# Werkstatt_Provisions_v_09.net
KiCad netlist of a schematic drawn in EAGLE
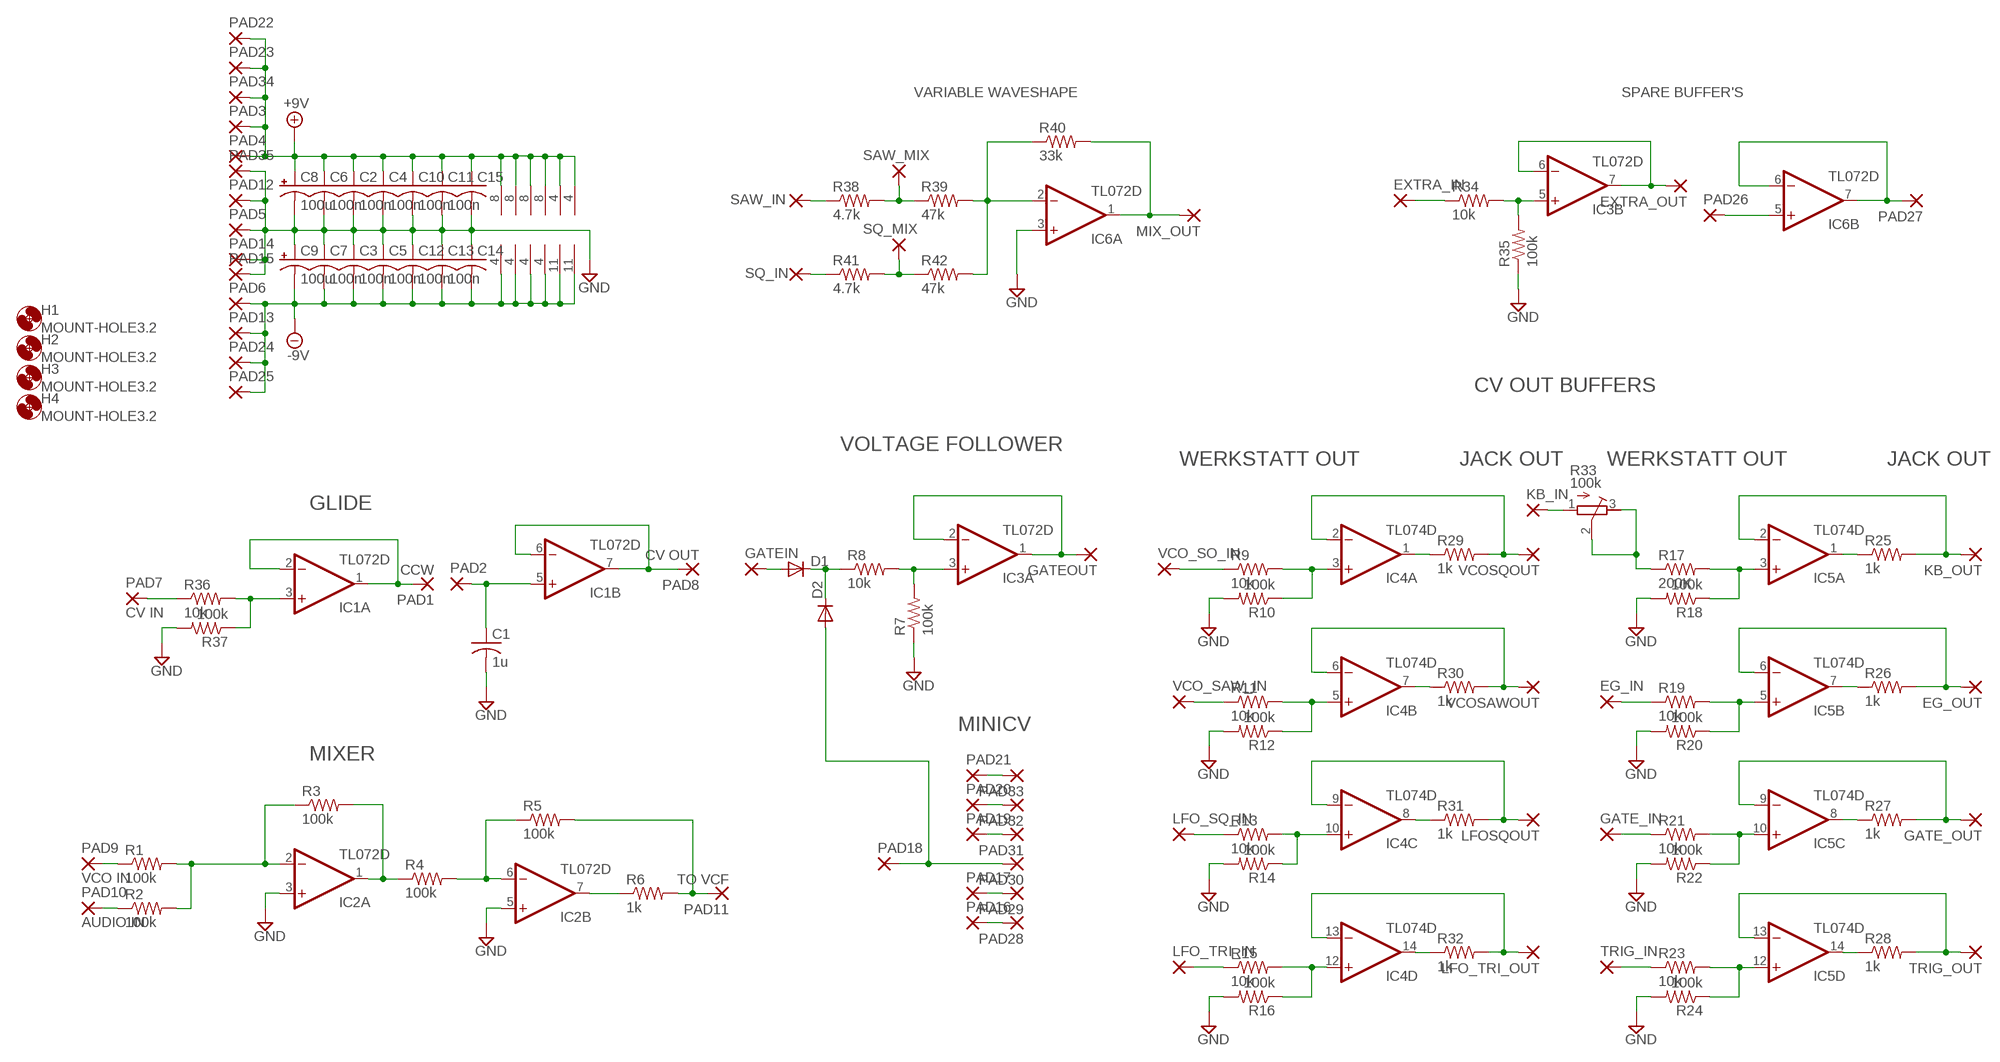
[diagram p0: schematic, sheet 1]

(export (version "E")
  (design (tool "Eeschema 10.0.6"))
  (components
    (comp (ref "C1")
      (value "1u")
      (footprint "eagle-import:C0805K")
      (libsource (lib "eagle-import") (part "C-USC0805K"))
    )
    (comp (ref "C2")
      (value "100n")
      (footprint "eagle-import:C0805K")
      (libsource (lib "eagle-import") (part "C-USC0805K"))
    )
    (comp (ref "C3")
      (value "100n")
      (footprint "eagle-import:C0805K")
      (libsource (lib "eagle-import") (part "C-USC0805K"))
    )
    (comp (ref "C4")
      (value "100n")
      (footprint "eagle-import:C0805K")
      (libsource (lib "eagle-import") (part "C-USC0805K"))
    )
    (comp (ref "C5")
      (value "100n")
      (footprint "eagle-import:C0805K")
      (libsource (lib "eagle-import") (part "C-USC0805K"))
    )
    (comp (ref "C6")
      (value "100n")
      (footprint "eagle-import:C0805K")
      (libsource (lib "eagle-import") (part "C-USC0805K"))
    )
    (comp (ref "C7")
      (value "100n")
      (footprint "eagle-import:C0805K")
      (libsource (lib "eagle-import") (part "C-USC0805K"))
    )
    (comp (ref "C8")
      (value "100u")
      (footprint "eagle-import:PANASONIC_D")
      (libsource (lib "eagle-import") (part "CPOL-USD"))
    )
    (comp (ref "C9")
      (value "100u")
      (footprint "eagle-import:PANASONIC_D")
      (libsource (lib "eagle-import") (part "CPOL-USD"))
    )
    (comp (ref "C10")
      (value "100n")
      (footprint "eagle-import:C0805K")
      (libsource (lib "eagle-import") (part "C-USC0805K"))
    )
    (comp (ref "C11")
      (value "100n")
      (footprint "eagle-import:C0805K")
      (libsource (lib "eagle-import") (part "C-USC0805K"))
    )
    (comp (ref "C12")
      (value "100n")
      (footprint "eagle-import:C0805K")
      (libsource (lib "eagle-import") (part "C-USC0805K"))
    )
    (comp (ref "C13")
      (value "100n")
      (footprint "eagle-import:C0805K")
      (libsource (lib "eagle-import") (part "C-USC0805K"))
    )
    (comp (ref "C14")
      (value "C-USC0805")
      (footprint "eagle-import:C0805")
      (libsource (lib "eagle-import") (part "C-USC0805"))
    )
    (comp (ref "C15")
      (value "C-USC0805")
      (footprint "eagle-import:C0805")
      (libsource (lib "eagle-import") (part "C-USC0805"))
    )
    (comp (ref "D1")
      (value "DIODE-SOD323-W")
      (footprint "eagle-import:SOD323-W")
      (libsource (lib "eagle-import") (part "DIODE-SOD323-W"))
    )
    (comp (ref "D2")
      (value "DIODE-SOD323-W")
      (footprint "eagle-import:SOD323-W")
      (libsource (lib "eagle-import") (part "DIODE-SOD323-W"))
    )
    (comp (ref "EG_IN")
      (value "2,0/0,9-O")
      (footprint "eagle-import:2,0_0,9-O")
      (libsource (lib "eagle-import") (part "2,0/0,9-O"))
    )
    (comp (ref "EG_OUT")
      (value "2,0/0,9-O")
      (footprint "eagle-import:2,0_0,9-O")
      (libsource (lib "eagle-import") (part "2,0/0,9-O"))
    )
    (comp (ref "EXTRA_IN")
      (value "2,0/0,9-O")
      (footprint "eagle-import:2,0_0,9-O")
      (libsource (lib "eagle-import") (part "2,0/0,9-O"))
    )
    (comp (ref "EXTRA_OUT")
      (value "2,0/0,9-O")
      (footprint "eagle-import:2,0_0,9-O")
      (libsource (lib "eagle-import") (part "2,0/0,9-O"))
    )
    (comp (ref "GATEIN")
      (value "2,0/0,9-O")
      (footprint "eagle-import:2,0_0,9-O")
      (libsource (lib "eagle-import") (part "2,0/0,9-O"))
    )
    (comp (ref "GATEOUT")
      (value "2,0/0,9-O")
      (footprint "eagle-import:2,0_0,9-O")
      (libsource (lib "eagle-import") (part "2,0/0,9-O"))
    )
    (comp (ref "GATE_IN")
      (value "2,0/0,9-O")
      (footprint "eagle-import:2,0_0,9-O")
      (libsource (lib "eagle-import") (part "2,0/0,9-O"))
    )
    (comp (ref "GATE_OUT")
      (value "2,0/0,9-O")
      (footprint "eagle-import:2,0_0,9-O")
      (libsource (lib "eagle-import") (part "2,0/0,9-O"))
    )
    (comp (ref "H1")
      (value "MOUNT-HOLE3.2")
      (footprint "eagle-import:3,2")
      (libsource (lib "eagle-import") (part "MOUNT-HOLE3.2"))
    )
    (comp (ref "H2")
      (value "MOUNT-HOLE3.2")
      (footprint "eagle-import:3,2")
      (libsource (lib "eagle-import") (part "MOUNT-HOLE3.2"))
    )
    (comp (ref "H3")
      (value "MOUNT-HOLE3.2")
      (footprint "eagle-import:3,2")
      (libsource (lib "eagle-import") (part "MOUNT-HOLE3.2"))
    )
    (comp (ref "H4")
      (value "MOUNT-HOLE3.2")
      (footprint "eagle-import:3,2")
      (libsource (lib "eagle-import") (part "MOUNT-HOLE3.2"))
    )
    (comp (ref "IC1")
      (value "TL072D")
      (footprint "eagle-import:SO08")
      (libsource (lib "eagle-import") (part "TL072D"))
    )
    (comp (ref "IC2")
      (value "TL072D")
      (footprint "eagle-import:SO08")
      (libsource (lib "eagle-import") (part "TL072D"))
    )
    (comp (ref "IC3")
      (value "TL072D")
      (footprint "eagle-import:SO08")
      (libsource (lib "eagle-import") (part "TL072D"))
    )
    (comp (ref "IC4")
      (value "TL074D")
      (footprint "eagle-import:SO14")
      (libsource (lib "eagle-import") (part "TL074D"))
    )
    (comp (ref "IC5")
      (value "TL074D")
      (footprint "eagle-import:SO14")
      (libsource (lib "eagle-import") (part "TL074D"))
    )
    (comp (ref "IC6")
      (value "TL072D")
      (footprint "eagle-import:SO08")
      (libsource (lib "eagle-import") (part "TL072D"))
    )
    (comp (ref "KB_IN")
      (value "2,0/0,9-O")
      (footprint "eagle-import:2,0_0,9-O")
      (libsource (lib "eagle-import") (part "2,0/0,9-O"))
    )
    (comp (ref "KB_OUT")
      (value "2,0/0,9-O")
      (footprint "eagle-import:2,0_0,9-O")
      (libsource (lib "eagle-import") (part "2,0/0,9-O"))
    )
    (comp (ref "LFOSQOUT")
      (value "2,0/0,9-O")
      (footprint "eagle-import:2,0_0,9-O")
      (libsource (lib "eagle-import") (part "2,0/0,9-O"))
    )
    (comp (ref "LFO_SQ_IN")
      (value "2,0/0,9-O")
      (footprint "eagle-import:2,0_0,9-O")
      (libsource (lib "eagle-import") (part "2,0/0,9-O"))
    )
    (comp (ref "LFO_TRI_IN")
      (value "2,0/0,9-O")
      (footprint "eagle-import:2,0_0,9-O")
      (libsource (lib "eagle-import") (part "2,0/0,9-O"))
    )
    (comp (ref "LFO_TRI_OUT")
      (value "2,0/0,9-O")
      (footprint "eagle-import:2,0_0,9-O")
      (libsource (lib "eagle-import") (part "2,0/0,9-O"))
    )
    (comp (ref "MIX_OUT")
      (value "2,0/0,9-O")
      (footprint "eagle-import:2,0_0,9-O")
      (libsource (lib "eagle-import") (part "2,0/0,9-O"))
    )
    (comp (ref "PAD1")
      (value "CCW")
      (footprint "eagle-import:2,0_0,9-O")
      (libsource (lib "eagle-import") (part "2,0/0,9-O"))
    )
    (comp (ref "PAD2")
      (value "2,0/0,9-O")
      (footprint "eagle-import:2,0_0,9-O")
      (libsource (lib "eagle-import") (part "2,0/0,9-O"))
    )
    (comp (ref "PAD3")
      (value "2,0/0,9-O")
      (footprint "eagle-import:2,0_0,9-O")
      (libsource (lib "eagle-import") (part "2,0/0,9-O"))
    )
    (comp (ref "PAD4")
      (value "2,0/0,9-O")
      (footprint "eagle-import:2,0_0,9-O")
      (libsource (lib "eagle-import") (part "2,0/0,9-O"))
    )
    (comp (ref "PAD5")
      (value "2,0/0,9-O")
      (footprint "eagle-import:2,0_0,9-O")
      (libsource (lib "eagle-import") (part "2,0/0,9-O"))
    )
    (comp (ref "PAD6")
      (value "2,0/0,9-O")
      (footprint "eagle-import:2,0_0,9-O")
      (libsource (lib "eagle-import") (part "2,0/0,9-O"))
    )
    (comp (ref "PAD7")
      (value "CV IN")
      (footprint "eagle-import:2,0_0,9-O")
      (libsource (lib "eagle-import") (part "2,0/0,9-O"))
    )
    (comp (ref "PAD8")
      (value "CV OUT")
      (footprint "eagle-import:2,0_0,9-O")
      (libsource (lib "eagle-import") (part "2,0/0,9-O"))
    )
    (comp (ref "PAD9")
      (value "VCO IN")
      (footprint "eagle-import:2,0_0,9-O")
      (libsource (lib "eagle-import") (part "2,0/0,9-O"))
    )
    (comp (ref "PAD10")
      (value "AUDIO IN")
      (footprint "eagle-import:2,0_0,9-O")
      (libsource (lib "eagle-import") (part "2,0/0,9-O"))
    )
    (comp (ref "PAD11")
      (value "TO VCF")
      (footprint "eagle-import:2,0_0,9-O")
      (libsource (lib "eagle-import") (part "2,0/0,9-O"))
    )
    (comp (ref "PAD12")
      (value "2,0/0,9-O")
      (footprint "eagle-import:2,0_0,9-O")
      (libsource (lib "eagle-import") (part "2,0/0,9-O"))
    )
    (comp (ref "PAD13")
      (value "2,0/0,9-O")
      (footprint "eagle-import:2,0_0,9-O")
      (libsource (lib "eagle-import") (part "2,0/0,9-O"))
    )
    (comp (ref "PAD14")
      (value "2,0/0,9-O")
      (footprint "eagle-import:2,0_0,9-O")
      (libsource (lib "eagle-import") (part "2,0/0,9-O"))
    )
    (comp (ref "PAD15")
      (value "2,0/0,9-O")
      (footprint "eagle-import:2,0_0,9-O")
      (libsource (lib "eagle-import") (part "2,0/0,9-O"))
    )
    (comp (ref "PAD16")
      (value "2,0/0,9-O")
      (footprint "eagle-import:2,0_0,9-O")
      (libsource (lib "eagle-import") (part "2,0/0,9-O"))
    )
    (comp (ref "PAD17")
      (value "2,0/0,9-O")
      (footprint "eagle-import:2,0_0,9-O")
      (libsource (lib "eagle-import") (part "2,0/0,9-O"))
    )
    (comp (ref "PAD18")
      (value "2,0/0,9-O")
      (footprint "eagle-import:2,0_0,9-O")
      (libsource (lib "eagle-import") (part "2,0/0,9-O"))
    )
    (comp (ref "PAD19")
      (value "2,0/0,9-O")
      (footprint "eagle-import:2,0_0,9-O")
      (libsource (lib "eagle-import") (part "2,0/0,9-O"))
    )
    (comp (ref "PAD20")
      (value "2,0/0,9-O")
      (footprint "eagle-import:2,0_0,9-O")
      (libsource (lib "eagle-import") (part "2,0/0,9-O"))
    )
    (comp (ref "PAD21")
      (value "2,0/0,9-O")
      (footprint "eagle-import:2,0_0,9-O")
      (libsource (lib "eagle-import") (part "2,0/0,9-O"))
    )
    (comp (ref "PAD22")
      (value "2,0/0,9-O")
      (footprint "eagle-import:2,0_0,9-O")
      (libsource (lib "eagle-import") (part "2,0/0,9-O"))
    )
    (comp (ref "PAD23")
      (value "2,0/0,9-O")
      (footprint "eagle-import:2,0_0,9-O")
      (libsource (lib "eagle-import") (part "2,0/0,9-O"))
    )
    (comp (ref "PAD24")
      (value "2,0/0,9-O")
      (footprint "eagle-import:2,0_0,9-O")
      (libsource (lib "eagle-import") (part "2,0/0,9-O"))
    )
    (comp (ref "PAD25")
      (value "2,0/0,9-O")
      (footprint "eagle-import:2,0_0,9-O")
      (libsource (lib "eagle-import") (part "2,0/0,9-O"))
    )
    (comp (ref "PAD26")
      (value "2,0/0,9-O")
      (footprint "eagle-import:2,0_0,9-O")
      (libsource (lib "eagle-import") (part "2,0/0,9-O"))
    )
    (comp (ref "PAD27")
      (value "2,0/0,9-O")
      (footprint "eagle-import:2,0_0,9-O")
      (libsource (lib "eagle-import") (part "2,0/0,9-O"))
    )
    (comp (ref "PAD28")
      (value "1,6/0,8")
      (footprint "eagle-import:1,6_0,8")
      (libsource (lib "eagle-import") (part "1,6/0,8"))
    )
    (comp (ref "PAD29")
      (value "1,6/0,8")
      (footprint "eagle-import:1,6_0,8")
      (libsource (lib "eagle-import") (part "1,6/0,8"))
    )
    (comp (ref "PAD30")
      (value "1,6/0,8")
      (footprint "eagle-import:1,6_0,8")
      (libsource (lib "eagle-import") (part "1,6/0,8"))
    )
    (comp (ref "PAD31")
      (value "1,6/0,8")
      (footprint "eagle-import:1,6_0,8")
      (libsource (lib "eagle-import") (part "1,6/0,8"))
    )
    (comp (ref "PAD32")
      (value "1,6/0,8")
      (footprint "eagle-import:1,6_0,8")
      (libsource (lib "eagle-import") (part "1,6/0,8"))
    )
    (comp (ref "PAD33")
      (value "1,6/0,8")
      (footprint "eagle-import:1,6_0,8")
      (libsource (lib "eagle-import") (part "1,6/0,8"))
    )
    (comp (ref "PAD34")
      (value "1,6/0,8")
      (footprint "eagle-import:1,6_0,8")
      (libsource (lib "eagle-import") (part "1,6/0,8"))
    )
    (comp (ref "PAD35")
      (value "1,6/0,8")
      (footprint "eagle-import:1,6_0,8")
      (libsource (lib "eagle-import") (part "1,6/0,8"))
    )
    (comp (ref "R1")
      (value "100k")
      (footprint "eagle-import:M0805")
      (libsource (lib "eagle-import") (part "R-US_M0805"))
    )
    (comp (ref "R2")
      (value "100k")
      (footprint "eagle-import:M0805")
      (libsource (lib "eagle-import") (part "R-US_M0805"))
    )
    (comp (ref "R3")
      (value "100k")
      (footprint "eagle-import:M0805")
      (libsource (lib "eagle-import") (part "R-US_M0805"))
    )
    (comp (ref "R4")
      (value "100k")
      (footprint "eagle-import:M0805")
      (libsource (lib "eagle-import") (part "R-US_M0805"))
    )
    (comp (ref "R5")
      (value "100k")
      (footprint "eagle-import:M0805")
      (libsource (lib "eagle-import") (part "R-US_M0805"))
    )
    (comp (ref "R6")
      (value "1k")
      (footprint "eagle-import:M0805")
      (libsource (lib "eagle-import") (part "R-US_M0805"))
    )
    (comp (ref "R7")
      (value "100k")
      (footprint "eagle-import:M0805")
      (libsource (lib "eagle-import") (part "R-US_M0805"))
    )
    (comp (ref "R8")
      (value "10k")
      (footprint "eagle-import:M0805")
      (libsource (lib "eagle-import") (part "R-US_M0805"))
    )
    (comp (ref "R9")
      (value "10k")
      (footprint "eagle-import:M0805")
      (libsource (lib "eagle-import") (part "R-US_M0805"))
    )
    (comp (ref "R10")
      (value "100k")
      (footprint "eagle-import:M0805")
      (libsource (lib "eagle-import") (part "R-US_M0805"))
    )
    (comp (ref "R11")
      (value "10k")
      (footprint "eagle-import:M0805")
      (libsource (lib "eagle-import") (part "R-US_M0805"))
    )
    (comp (ref "R12")
      (value "100k")
      (footprint "eagle-import:M0805")
      (libsource (lib "eagle-import") (part "R-US_M0805"))
    )
    (comp (ref "R13")
      (value "10k")
      (footprint "eagle-import:M0805")
      (libsource (lib "eagle-import") (part "R-US_M0805"))
    )
    (comp (ref "R14")
      (value "100k")
      (footprint "eagle-import:M0805")
      (libsource (lib "eagle-import") (part "R-US_M0805"))
    )
    (comp (ref "R15")
      (value "10k")
      (footprint "eagle-import:M0805")
      (libsource (lib "eagle-import") (part "R-US_M0805"))
    )
    (comp (ref "R16")
      (value "100k")
      (footprint "eagle-import:M0805")
      (libsource (lib "eagle-import") (part "R-US_M0805"))
    )
    (comp (ref "R17")
      (value "200K")
      (footprint "eagle-import:M0805")
      (libsource (lib "eagle-import") (part "R-US_M0805"))
    )
    (comp (ref "R18")
      (value "100k")
      (footprint "eagle-import:M0805")
      (libsource (lib "eagle-import") (part "R-US_M0805"))
    )
    (comp (ref "R19")
      (value "10k")
      (footprint "eagle-import:M0805")
      (libsource (lib "eagle-import") (part "R-US_M0805"))
    )
    (comp (ref "R20")
      (value "100k")
      (footprint "eagle-import:M0805")
      (libsource (lib "eagle-import") (part "R-US_M0805"))
    )
    (comp (ref "R21")
      (value "10k")
      (footprint "eagle-import:M0805")
      (libsource (lib "eagle-import") (part "R-US_M0805"))
    )
    (comp (ref "R22")
      (value "100k")
      (footprint "eagle-import:M0805")
      (libsource (lib "eagle-import") (part "R-US_M0805"))
    )
    (comp (ref "R23")
      (value "10k")
      (footprint "eagle-import:M0805")
      (libsource (lib "eagle-import") (part "R-US_M0805"))
    )
    (comp (ref "R24")
      (value "100k")
      (footprint "eagle-import:M0805")
      (libsource (lib "eagle-import") (part "R-US_M0805"))
    )
    (comp (ref "R25")
      (value "1k")
      (footprint "eagle-import:M0805")
      (libsource (lib "eagle-import") (part "R-US_M0805"))
    )
    (comp (ref "R26")
      (value "1k")
      (footprint "eagle-import:M0805")
      (libsource (lib "eagle-import") (part "R-US_M0805"))
    )
    (comp (ref "R27")
      (value "1k")
      (footprint "eagle-import:M0805")
      (libsource (lib "eagle-import") (part "R-US_M0805"))
    )
    (comp (ref "R28")
      (value "1k")
      (footprint "eagle-import:M0805")
      (libsource (lib "eagle-import") (part "R-US_M0805"))
    )
    (comp (ref "R29")
      (value "1k")
      (footprint "eagle-import:M0805")
      (libsource (lib "eagle-import") (part "R-US_M0805"))
    )
    (comp (ref "R30")
      (value "1k")
      (footprint "eagle-import:M0805")
      (libsource (lib "eagle-import") (part "R-US_M0805"))
    )
    (comp (ref "R31")
      (value "1k")
      (footprint "eagle-import:M0805")
      (libsource (lib "eagle-import") (part "R-US_M0805"))
    )
    (comp (ref "R32")
      (value "1k")
      (footprint "eagle-import:M0805")
      (libsource (lib "eagle-import") (part "R-US_M0805"))
    )
    (comp (ref "R33")
      (value "100k")
      (footprint "eagle-import:RTRIM3202")
      (libsource (lib "eagle-import") (part "R-TRIMM3202"))
    )
    (comp (ref "R34")
      (value "10k")
      (footprint "eagle-import:M0805")
      (libsource (lib "eagle-import") (part "R-US_M0805"))
    )
    (comp (ref "R35")
      (value "100k")
      (footprint "eagle-import:M0805")
      (libsource (lib "eagle-import") (part "R-US_M0805"))
    )
    (comp (ref "R36")
      (value "10k")
      (footprint "eagle-import:M0805")
      (libsource (lib "eagle-import") (part "R-US_M0805"))
    )
    (comp (ref "R37")
      (value "100k")
      (footprint "eagle-import:M0805")
      (libsource (lib "eagle-import") (part "R-US_M0805"))
    )
    (comp (ref "R38")
      (value "4.7k")
      (footprint "eagle-import:R0805")
      (libsource (lib "eagle-import") (part "R-US_R0805"))
    )
    (comp (ref "R39")
      (value "47k")
      (footprint "eagle-import:R0805")
      (libsource (lib "eagle-import") (part "R-US_R0805"))
    )
    (comp (ref "R40")
      (value "33k")
      (footprint "eagle-import:R0805")
      (libsource (lib "eagle-import") (part "R-US_R0805"))
    )
    (comp (ref "R41")
      (value "4.7k")
      (footprint "eagle-import:R0805")
      (libsource (lib "eagle-import") (part "R-US_R0805"))
    )
    (comp (ref "R42")
      (value "47k")
      (footprint "eagle-import:R0805")
      (libsource (lib "eagle-import") (part "R-US_R0805"))
    )
    (comp (ref "SAW_IN")
      (value "2,0/0,9-O")
      (footprint "eagle-import:2,0_0,9-O")
      (libsource (lib "eagle-import") (part "2,0/0,9-O"))
    )
    (comp (ref "SAW_MIX")
      (value "2,0/0,9-O")
      (footprint "eagle-import:2,0_0,9-O")
      (libsource (lib "eagle-import") (part "2,0/0,9-O"))
    )
    (comp (ref "SQ_IN")
      (value "2,0/0,9-O")
      (footprint "eagle-import:2,0_0,9-O")
      (libsource (lib "eagle-import") (part "2,0/0,9-O"))
    )
    (comp (ref "SQ_MIX")
      (value "2,0/0,9-O")
      (footprint "eagle-import:2,0_0,9-O")
      (libsource (lib "eagle-import") (part "2,0/0,9-O"))
    )
    (comp (ref "TRIG_IN")
      (value "2,0/0,9-O")
      (footprint "eagle-import:2,0_0,9-O")
      (libsource (lib "eagle-import") (part "2,0/0,9-O"))
    )
    (comp (ref "TRIG_OUT")
      (value "2,0/0,9-O")
      (footprint "eagle-import:2,0_0,9-O")
      (libsource (lib "eagle-import") (part "2,0/0,9-O"))
    )
    (comp (ref "VCOSAWOUT")
      (value "2,0/0,9-O")
      (footprint "eagle-import:2,0_0,9-O")
      (libsource (lib "eagle-import") (part "2,0/0,9-O"))
    )
    (comp (ref "VCOSQOUT")
      (value "2,0/0,9-O")
      (footprint "eagle-import:2,0_0,9-O")
      (libsource (lib "eagle-import") (part "2,0/0,9-O"))
    )
    (comp (ref "VCO_SAW_IN")
      (value "2,0/0,9-O")
      (footprint "eagle-import:2,0_0,9-O")
      (libsource (lib "eagle-import") (part "2,0/0,9-O"))
    )
    (comp (ref "VCO_SO_IN")
      (value "2,0/0,9-O")
      (footprint "eagle-import:2,0_0,9-O")
      (libsource (lib "eagle-import") (part "2,0/0,9-O"))
    )
  )
  (nets
    (net (code "1") (name "+9V") (class "Default")
      (node (ref "C10") (pin "1") (pinfunction "1_1") (pintype "passive"))
      (node (ref "C11") (pin "1") (pinfunction "1_1") (pintype "passive"))
      (node (ref "C15") (pin "1") (pinfunction "1_1") (pintype "passive"))
      (node (ref "C2") (pin "1") (pinfunction "1_1") (pintype "passive"))
      (node (ref "C4") (pin "1") (pinfunction "1_1") (pintype "passive"))
      (node (ref "C6") (pin "1") (pinfunction "1_1") (pintype "passive"))
      (node (ref "C8") (pin "+") (pinfunction "+_+") (pintype "passive"))
      (node (ref "IC1") (pin "8") (pinfunction "V+_8") (pintype "power_in"))
      (node (ref "IC2") (pin "8") (pinfunction "V+_8") (pintype "power_in"))
      (node (ref "IC3") (pin "8") (pinfunction "V+_8") (pintype "power_in"))
      (node (ref "IC4") (pin "4") (pinfunction "V+_4") (pintype "power_in"))
      (node (ref "IC5") (pin "4") (pinfunction "V+_4") (pintype "power_in"))
      (node (ref "IC6") (pin "8") (pinfunction "V+_8") (pintype "power_in"))
      (node (ref "PAD22") (pin "1") (pinfunction "P_1") (pintype "passive"))
      (node (ref "PAD23") (pin "1") (pinfunction "P_1") (pintype "passive"))
      (node (ref "PAD3") (pin "1") (pinfunction "P_1") (pintype "passive"))
      (node (ref "PAD34") (pin "1") (pinfunction "P_1") (pintype "passive"))
      (node (ref "PAD4") (pin "1") (pinfunction "P_1") (pintype "passive"))
    )
    (net (code "2") (name "-9V") (class "Default")
      (node (ref "C12") (pin "2") (pinfunction "2_2") (pintype "passive"))
      (node (ref "C13") (pin "2") (pinfunction "2_2") (pintype "passive"))
      (node (ref "C14") (pin "2") (pinfunction "2_2") (pintype "passive"))
      (node (ref "C3") (pin "2") (pinfunction "2_2") (pintype "passive"))
      (node (ref "C5") (pin "2") (pinfunction "2_2") (pintype "passive"))
      (node (ref "C7") (pin "2") (pinfunction "2_2") (pintype "passive"))
      (node (ref "C9") (pin "-") (pinfunction "-_-") (pintype "passive"))
      (node (ref "IC1") (pin "4") (pinfunction "V-_4") (pintype "power_in"))
      (node (ref "IC2") (pin "4") (pinfunction "V-_4") (pintype "power_in"))
      (node (ref "IC3") (pin "4") (pinfunction "V-_4") (pintype "power_in"))
      (node (ref "IC4") (pin "11") (pinfunction "V-_11") (pintype "power_in"))
      (node (ref "IC5") (pin "11") (pinfunction "V-_11") (pintype "power_in"))
      (node (ref "IC6") (pin "4") (pinfunction "V-_4") (pintype "power_in"))
      (node (ref "PAD13") (pin "1") (pinfunction "P_1") (pintype "passive"))
      (node (ref "PAD24") (pin "1") (pinfunction "P_1") (pintype "passive"))
      (node (ref "PAD25") (pin "1") (pinfunction "P_1") (pintype "passive"))
      (node (ref "PAD6") (pin "1") (pinfunction "P_1") (pintype "passive"))
    )
    (net (code "3") (name "GND") (class "Default")
      (node (ref "C1") (pin "2") (pinfunction "2_2") (pintype "passive"))
      (node (ref "C10") (pin "2") (pinfunction "2_2") (pintype "passive"))
      (node (ref "C11") (pin "2") (pinfunction "2_2") (pintype "passive"))
      (node (ref "C12") (pin "1") (pinfunction "1_1") (pintype "passive"))
      (node (ref "C13") (pin "1") (pinfunction "1_1") (pintype "passive"))
      (node (ref "C14") (pin "1") (pinfunction "1_1") (pintype "passive"))
      (node (ref "C15") (pin "2") (pinfunction "2_2") (pintype "passive"))
      (node (ref "C2") (pin "2") (pinfunction "2_2") (pintype "passive"))
      (node (ref "C3") (pin "1") (pinfunction "1_1") (pintype "passive"))
      (node (ref "C4") (pin "2") (pinfunction "2_2") (pintype "passive"))
      (node (ref "C5") (pin "1") (pinfunction "1_1") (pintype "passive"))
      (node (ref "C6") (pin "2") (pinfunction "2_2") (pintype "passive"))
      (node (ref "C7") (pin "1") (pinfunction "1_1") (pintype "passive"))
      (node (ref "C8") (pin "-") (pinfunction "-_-") (pintype "passive"))
      (node (ref "C9") (pin "+") (pinfunction "+_+") (pintype "passive"))
      (node (ref "IC2") (pin "3") (pinfunction "+IN_3") (pintype "input"))
      (node (ref "IC2") (pin "5") (pinfunction "+IN_5") (pintype "input"))
      (node (ref "IC6") (pin "3") (pinfunction "+IN_3") (pintype "input"))
      (node (ref "PAD12") (pin "1") (pinfunction "P_1") (pintype "passive"))
      (node (ref "PAD14") (pin "1") (pinfunction "P_1") (pintype "passive"))
      (node (ref "PAD15") (pin "1") (pinfunction "P_1") (pintype "passive"))
      (node (ref "PAD35") (pin "1") (pinfunction "P_1") (pintype "passive"))
      (node (ref "PAD5") (pin "1") (pinfunction "P_1") (pintype "passive"))
      (node (ref "R10") (pin "2") (pinfunction "2_2") (pintype "passive"))
      (node (ref "R12") (pin "2") (pinfunction "2_2") (pintype "passive"))
      (node (ref "R14") (pin "2") (pinfunction "2_2") (pintype "passive"))
      (node (ref "R16") (pin "2") (pinfunction "2_2") (pintype "passive"))
      (node (ref "R18") (pin "2") (pinfunction "2_2") (pintype "passive"))
      (node (ref "R20") (pin "2") (pinfunction "2_2") (pintype "passive"))
      (node (ref "R22") (pin "2") (pinfunction "2_2") (pintype "passive"))
      (node (ref "R24") (pin "2") (pinfunction "2_2") (pintype "passive"))
      (node (ref "R35") (pin "1") (pinfunction "1_1") (pintype "passive"))
      (node (ref "R37") (pin "2") (pinfunction "2_2") (pintype "passive"))
      (node (ref "R7") (pin "1") (pinfunction "1_1") (pintype "passive"))
    )
    (net (code "4") (name "Net-(D1-PadC)") (class "Default")
      (node (ref "D1") (pin "C") (pinfunction "C_C") (pintype "passive"))
      (node (ref "D2") (pin "C") (pinfunction "C_C") (pintype "passive"))
      (node (ref "R8") (pin "1") (pinfunction "1_1") (pintype "passive"))
    )
    (net (code "5") (name "Net-(EG_IN-P)") (class "Default")
      (node (ref "EG_IN") (pin "1") (pinfunction "P_1") (pintype "passive"))
      (node (ref "R19") (pin "1") (pinfunction "1_1") (pintype "passive"))
    )
    (net (code "6") (name "Net-(EG_OUT-P)") (class "Default")
      (node (ref "EG_OUT") (pin "1") (pinfunction "P_1") (pintype "passive"))
      (node (ref "IC5") (pin "6") (pinfunction "-IN_6") (pintype "input"))
      (node (ref "R26") (pin "2") (pinfunction "2_2") (pintype "passive"))
    )
    (net (code "7") (name "Net-(EXTRA_IN-P)") (class "Default")
      (node (ref "EXTRA_IN") (pin "1") (pinfunction "P_1") (pintype "passive"))
      (node (ref "R34") (pin "1") (pinfunction "1_1") (pintype "passive"))
    )
    (net (code "8") (name "Net-(EXTRA_OUT-P)") (class "Default")
      (node (ref "EXTRA_OUT") (pin "1") (pinfunction "P_1") (pintype "passive"))
      (node (ref "IC3") (pin "6") (pinfunction "-IN_6") (pintype "input"))
      (node (ref "IC3") (pin "7") (pinfunction "OUT_7") (pintype "output"))
    )
    (net (code "9") (name "Net-(GATEIN-P)") (class "Default")
      (node (ref "D1") (pin "A") (pinfunction "A_A") (pintype "passive"))
      (node (ref "GATEIN") (pin "1") (pinfunction "P_1") (pintype "passive"))
    )
    (net (code "10") (name "Net-(GATEOUT-P)") (class "Default")
      (node (ref "GATEOUT") (pin "1") (pinfunction "P_1") (pintype "passive"))
      (node (ref "IC3") (pin "1") (pinfunction "OUT_1") (pintype "output"))
      (node (ref "IC3") (pin "2") (pinfunction "-IN_2") (pintype "input"))
    )
    (net (code "11") (name "Net-(GATE_IN-P)") (class "Default")
      (node (ref "GATE_IN") (pin "1") (pinfunction "P_1") (pintype "passive"))
      (node (ref "R21") (pin "1") (pinfunction "1_1") (pintype "passive"))
    )
    (net (code "12") (name "Net-(GATE_OUT-P)") (class "Default")
      (node (ref "GATE_OUT") (pin "1") (pinfunction "P_1") (pintype "passive"))
      (node (ref "IC5") (pin "9") (pinfunction "-IN_9") (pintype "input"))
      (node (ref "R27") (pin "2") (pinfunction "2_2") (pintype "passive"))
    )
    (net (code "13") (name "Net-(IC1A-+IN)") (class "Default")
      (node (ref "IC1") (pin "3") (pinfunction "+IN_3") (pintype "input"))
      (node (ref "R36") (pin "2") (pinfunction "2_2") (pintype "passive"))
      (node (ref "R37") (pin "1") (pinfunction "1_1") (pintype "passive"))
    )
    (net (code "14") (name "Net-(IC1A--IN)") (class "Default")
      (node (ref "IC1") (pin "1") (pinfunction "OUT_1") (pintype "output"))
      (node (ref "IC1") (pin "2") (pinfunction "-IN_2") (pintype "input"))
      (node (ref "PAD1") (pin "1") (pinfunction "P_1") (pintype "passive"))
    )
    (net (code "15") (name "Net-(IC1B-+IN)") (class "Default")
      (node (ref "C1") (pin "1") (pinfunction "1_1") (pintype "passive"))
      (node (ref "IC1") (pin "5") (pinfunction "+IN_5") (pintype "input"))
      (node (ref "PAD2") (pin "1") (pinfunction "P_1") (pintype "passive"))
    )
    (net (code "16") (name "Net-(IC1B--IN)") (class "Default")
      (node (ref "IC1") (pin "6") (pinfunction "-IN_6") (pintype "input"))
      (node (ref "IC1") (pin "7") (pinfunction "OUT_7") (pintype "output"))
      (node (ref "PAD8") (pin "1") (pinfunction "P_1") (pintype "passive"))
    )
    (net (code "17") (name "Net-(IC2A--IN)") (class "Default")
      (node (ref "IC2") (pin "2") (pinfunction "-IN_2") (pintype "input"))
      (node (ref "R1") (pin "2") (pinfunction "2_2") (pintype "passive"))
      (node (ref "R2") (pin "2") (pinfunction "2_2") (pintype "passive"))
      (node (ref "R3") (pin "1") (pinfunction "1_1") (pintype "passive"))
    )
    (net (code "18") (name "Net-(IC2A-OUT)") (class "Default")
      (node (ref "IC2") (pin "1") (pinfunction "OUT_1") (pintype "output"))
      (node (ref "R3") (pin "2") (pinfunction "2_2") (pintype "passive"))
      (node (ref "R4") (pin "1") (pinfunction "1_1") (pintype "passive"))
    )
    (net (code "19") (name "Net-(IC2B--IN)") (class "Default")
      (node (ref "IC2") (pin "6") (pinfunction "-IN_6") (pintype "input"))
      (node (ref "R4") (pin "2") (pinfunction "2_2") (pintype "passive"))
      (node (ref "R5") (pin "1") (pinfunction "1_1") (pintype "passive"))
    )
    (net (code "20") (name "Net-(IC2B-OUT)") (class "Default")
      (node (ref "IC2") (pin "7") (pinfunction "OUT_7") (pintype "output"))
      (node (ref "R6") (pin "1") (pinfunction "1_1") (pintype "passive"))
    )
    (net (code "21") (name "Net-(IC3A-+IN)") (class "Default")
      (node (ref "IC3") (pin "3") (pinfunction "+IN_3") (pintype "input"))
      (node (ref "R7") (pin "2") (pinfunction "2_2") (pintype "passive"))
      (node (ref "R8") (pin "2") (pinfunction "2_2") (pintype "passive"))
    )
    (net (code "22") (name "Net-(IC3B-+IN)") (class "Default")
      (node (ref "IC3") (pin "5") (pinfunction "+IN_5") (pintype "input"))
      (node (ref "R34") (pin "2") (pinfunction "2_2") (pintype "passive"))
      (node (ref "R35") (pin "2") (pinfunction "2_2") (pintype "passive"))
    )
    (net (code "23") (name "Net-(IC4A-+IN)") (class "Default")
      (node (ref "IC4") (pin "3") (pinfunction "+IN_3") (pintype "input"))
      (node (ref "R10") (pin "1") (pinfunction "1_1") (pintype "passive"))
      (node (ref "R9") (pin "2") (pinfunction "2_2") (pintype "passive"))
    )
    (net (code "24") (name "Net-(IC4A--IN)") (class "Default")
      (node (ref "IC4") (pin "2") (pinfunction "-IN_2") (pintype "input"))
      (node (ref "R29") (pin "2") (pinfunction "2_2") (pintype "passive"))
      (node (ref "VCOSQOUT") (pin "1") (pinfunction "P_1") (pintype "passive"))
    )
    (net (code "25") (name "Net-(IC4A-OUT)") (class "Default")
      (node (ref "IC4") (pin "1") (pinfunction "OUT_1") (pintype "output"))
      (node (ref "R29") (pin "1") (pinfunction "1_1") (pintype "passive"))
    )
    (net (code "26") (name "Net-(IC4B-+IN)") (class "Default")
      (node (ref "IC4") (pin "5") (pinfunction "+IN_5") (pintype "input"))
      (node (ref "R11") (pin "2") (pinfunction "2_2") (pintype "passive"))
      (node (ref "R12") (pin "1") (pinfunction "1_1") (pintype "passive"))
    )
    (net (code "27") (name "Net-(IC4B--IN)") (class "Default")
      (node (ref "IC4") (pin "6") (pinfunction "-IN_6") (pintype "input"))
      (node (ref "R30") (pin "2") (pinfunction "2_2") (pintype "passive"))
      (node (ref "VCOSAWOUT") (pin "1") (pinfunction "P_1") (pintype "passive"))
    )
    (net (code "28") (name "Net-(IC4B-OUT)") (class "Default")
      (node (ref "IC4") (pin "7") (pinfunction "OUT_7") (pintype "output"))
      (node (ref "R30") (pin "1") (pinfunction "1_1") (pintype "passive"))
    )
    (net (code "29") (name "Net-(IC4C-+IN)") (class "Default")
      (node (ref "IC4") (pin "10") (pinfunction "+IN_10") (pintype "input"))
      (node (ref "R13") (pin "2") (pinfunction "2_2") (pintype "passive"))
      (node (ref "R14") (pin "1") (pinfunction "1_1") (pintype "passive"))
    )
    (net (code "30") (name "Net-(IC4C--IN)") (class "Default")
      (node (ref "IC4") (pin "9") (pinfunction "-IN_9") (pintype "input"))
      (node (ref "LFOSQOUT") (pin "1") (pinfunction "P_1") (pintype "passive"))
      (node (ref "R31") (pin "2") (pinfunction "2_2") (pintype "passive"))
    )
    (net (code "31") (name "Net-(IC4C-OUT)") (class "Default")
      (node (ref "IC4") (pin "8") (pinfunction "OUT_8") (pintype "output"))
      (node (ref "R31") (pin "1") (pinfunction "1_1") (pintype "passive"))
    )
    (net (code "32") (name "Net-(IC4D-+IN)") (class "Default")
      (node (ref "IC4") (pin "12") (pinfunction "+IN_12") (pintype "input"))
      (node (ref "R15") (pin "2") (pinfunction "2_2") (pintype "passive"))
      (node (ref "R16") (pin "1") (pinfunction "1_1") (pintype "passive"))
    )
    (net (code "33") (name "Net-(IC4D--IN)") (class "Default")
      (node (ref "IC4") (pin "13") (pinfunction "-IN_13") (pintype "input"))
      (node (ref "LFO_TRI_OUT") (pin "1") (pinfunction "P_1") (pintype "passive"))
      (node (ref "R32") (pin "2") (pinfunction "2_2") (pintype "passive"))
    )
    (net (code "34") (name "Net-(IC4D-OUT)") (class "Default")
      (node (ref "IC4") (pin "14") (pinfunction "OUT_14") (pintype "output"))
      (node (ref "R32") (pin "1") (pinfunction "1_1") (pintype "passive"))
    )
    (net (code "35") (name "Net-(IC5A-+IN)") (class "Default")
      (node (ref "IC5") (pin "3") (pinfunction "+IN_3") (pintype "input"))
      (node (ref "R17") (pin "2") (pinfunction "2_2") (pintype "passive"))
      (node (ref "R18") (pin "1") (pinfunction "1_1") (pintype "passive"))
    )
    (net (code "36") (name "Net-(IC5A--IN)") (class "Default")
      (node (ref "IC5") (pin "2") (pinfunction "-IN_2") (pintype "input"))
      (node (ref "KB_OUT") (pin "1") (pinfunction "P_1") (pintype "passive"))
      (node (ref "R25") (pin "2") (pinfunction "2_2") (pintype "passive"))
    )
    (net (code "37") (name "Net-(IC5A-OUT)") (class "Default")
      (node (ref "IC5") (pin "1") (pinfunction "OUT_1") (pintype "output"))
      (node (ref "R25") (pin "1") (pinfunction "1_1") (pintype "passive"))
    )
    (net (code "38") (name "Net-(IC5B-+IN)") (class "Default")
      (node (ref "IC5") (pin "5") (pinfunction "+IN_5") (pintype "input"))
      (node (ref "R19") (pin "2") (pinfunction "2_2") (pintype "passive"))
      (node (ref "R20") (pin "1") (pinfunction "1_1") (pintype "passive"))
    )
    (net (code "39") (name "Net-(IC5B-OUT)") (class "Default")
      (node (ref "IC5") (pin "7") (pinfunction "OUT_7") (pintype "output"))
      (node (ref "R26") (pin "1") (pinfunction "1_1") (pintype "passive"))
    )
    (net (code "40") (name "Net-(IC5C-+IN)") (class "Default")
      (node (ref "IC5") (pin "10") (pinfunction "+IN_10") (pintype "input"))
      (node (ref "R21") (pin "2") (pinfunction "2_2") (pintype "passive"))
      (node (ref "R22") (pin "1") (pinfunction "1_1") (pintype "passive"))
    )
    (net (code "41") (name "Net-(IC5C-OUT)") (class "Default")
      (node (ref "IC5") (pin "8") (pinfunction "OUT_8") (pintype "output"))
      (node (ref "R27") (pin "1") (pinfunction "1_1") (pintype "passive"))
    )
    (net (code "42") (name "Net-(IC5D-+IN)") (class "Default")
      (node (ref "IC5") (pin "12") (pinfunction "+IN_12") (pintype "input"))
      (node (ref "R23") (pin "2") (pinfunction "2_2") (pintype "passive"))
      (node (ref "R24") (pin "1") (pinfunction "1_1") (pintype "passive"))
    )
    (net (code "43") (name "Net-(IC5D--IN)") (class "Default")
      (node (ref "IC5") (pin "13") (pinfunction "-IN_13") (pintype "input"))
      (node (ref "R28") (pin "2") (pinfunction "2_2") (pintype "passive"))
      (node (ref "TRIG_OUT") (pin "1") (pinfunction "P_1") (pintype "passive"))
    )
    (net (code "44") (name "Net-(IC5D-OUT)") (class "Default")
      (node (ref "IC5") (pin "14") (pinfunction "OUT_14") (pintype "output"))
      (node (ref "R28") (pin "1") (pinfunction "1_1") (pintype "passive"))
    )
    (net (code "45") (name "Net-(IC6A--IN)") (class "Default")
      (node (ref "IC6") (pin "2") (pinfunction "-IN_2") (pintype "input"))
      (node (ref "R39") (pin "2") (pinfunction "2_2") (pintype "passive"))
      (node (ref "R40") (pin "1") (pinfunction "1_1") (pintype "passive"))
      (node (ref "R42") (pin "2") (pinfunction "2_2") (pintype "passive"))
    )
    (net (code "46") (name "Net-(IC6A-OUT)") (class "Default")
      (node (ref "IC6") (pin "1") (pinfunction "OUT_1") (pintype "output"))
      (node (ref "MIX_OUT") (pin "1") (pinfunction "P_1") (pintype "passive"))
      (node (ref "R40") (pin "2") (pinfunction "2_2") (pintype "passive"))
    )
    (net (code "47") (name "Net-(IC6B-+IN)") (class "Default")
      (node (ref "IC6") (pin "5") (pinfunction "+IN_5") (pintype "input"))
      (node (ref "PAD26") (pin "1") (pinfunction "P_1") (pintype "passive"))
    )
    (net (code "48") (name "Net-(IC6B--IN)") (class "Default")
      (node (ref "IC6") (pin "6") (pinfunction "-IN_6") (pintype "input"))
      (node (ref "IC6") (pin "7") (pinfunction "OUT_7") (pintype "output"))
      (node (ref "PAD27") (pin "1") (pinfunction "P_1") (pintype "passive"))
    )
    (net (code "49") (name "Net-(KB_IN-P)") (class "Default")
      (node (ref "KB_IN") (pin "1") (pinfunction "P_1") (pintype "passive"))
      (node (ref "R33") (pin "1") (pinfunction "E_1") (pintype "passive"))
    )
    (net (code "50") (name "Net-(LFO_SQ_IN-P)") (class "Default")
      (node (ref "LFO_SQ_IN") (pin "1") (pinfunction "P_1") (pintype "passive"))
      (node (ref "R13") (pin "1") (pinfunction "1_1") (pintype "passive"))
    )
    (net (code "51") (name "Net-(LFO_TRI_IN-P)") (class "Default")
      (node (ref "LFO_TRI_IN") (pin "1") (pinfunction "P_1") (pintype "passive"))
      (node (ref "R15") (pin "1") (pinfunction "1_1") (pintype "passive"))
    )
    (net (code "52") (name "Net-(PAD7-P)") (class "Default")
      (node (ref "PAD7") (pin "1") (pinfunction "P_1") (pintype "passive"))
      (node (ref "R36") (pin "1") (pinfunction "1_1") (pintype "passive"))
    )
    (net (code "53") (name "Net-(PAD9-P)") (class "Default")
      (node (ref "PAD9") (pin "1") (pinfunction "P_1") (pintype "passive"))
      (node (ref "R1") (pin "1") (pinfunction "1_1") (pintype "passive"))
    )
    (net (code "54") (name "Net-(PAD10-P)") (class "Default")
      (node (ref "PAD10") (pin "1") (pinfunction "P_1") (pintype "passive"))
      (node (ref "R2") (pin "1") (pinfunction "1_1") (pintype "passive"))
    )
    (net (code "55") (name "Net-(PAD11-P)") (class "Default")
      (node (ref "PAD11") (pin "1") (pinfunction "P_1") (pintype "passive"))
      (node (ref "R5") (pin "2") (pinfunction "2_2") (pintype "passive"))
      (node (ref "R6") (pin "2") (pinfunction "2_2") (pintype "passive"))
    )
    (net (code "56") (name "Net-(PAD16-P)") (class "Default")
      (node (ref "PAD16") (pin "1") (pinfunction "P_1") (pintype "passive"))
      (node (ref "PAD28") (pin "1") (pinfunction "P_1") (pintype "passive"))
    )
    (net (code "57") (name "Net-(PAD17-P)") (class "Default")
      (node (ref "PAD17") (pin "1") (pinfunction "P_1") (pintype "passive"))
      (node (ref "PAD29") (pin "1") (pinfunction "P_1") (pintype "passive"))
    )
    (net (code "58") (name "Net-(PAD18-P)") (class "Default")
      (node (ref "D2") (pin "A") (pinfunction "A_A") (pintype "passive"))
      (node (ref "PAD18") (pin "1") (pinfunction "P_1") (pintype "passive"))
      (node (ref "PAD30") (pin "1") (pinfunction "P_1") (pintype "passive"))
    )
    (net (code "59") (name "Net-(PAD19-P)") (class "Default")
      (node (ref "PAD19") (pin "1") (pinfunction "P_1") (pintype "passive"))
      (node (ref "PAD31") (pin "1") (pinfunction "P_1") (pintype "passive"))
    )
    (net (code "60") (name "Net-(PAD20-P)") (class "Default")
      (node (ref "PAD20") (pin "1") (pinfunction "P_1") (pintype "passive"))
      (node (ref "PAD32") (pin "1") (pinfunction "P_1") (pintype "passive"))
    )
    (net (code "61") (name "Net-(PAD21-P)") (class "Default")
      (node (ref "PAD21") (pin "1") (pinfunction "P_1") (pintype "passive"))
      (node (ref "PAD33") (pin "1") (pinfunction "P_1") (pintype "passive"))
    )
    (net (code "62") (name "Net-(R33-A)") (class "Default")
      (node (ref "R17") (pin "1") (pinfunction "1_1") (pintype "passive"))
      (node (ref "R33") (pin "2") (pinfunction "S_2") (pintype "passive"))
      (node (ref "R33") (pin "3") (pinfunction "A_3") (pintype "passive"))
    )
    (net (code "63") (name "Net-(SAW_IN-P)") (class "Default")
      (node (ref "R38") (pin "1") (pinfunction "1_1") (pintype "passive"))
      (node (ref "SAW_IN") (pin "1") (pinfunction "P_1") (pintype "passive"))
    )
    (net (code "64") (name "Net-(SAW_MIX-P)") (class "Default")
      (node (ref "R38") (pin "2") (pinfunction "2_2") (pintype "passive"))
      (node (ref "R39") (pin "1") (pinfunction "1_1") (pintype "passive"))
      (node (ref "SAW_MIX") (pin "1") (pinfunction "P_1") (pintype "passive"))
    )
    (net (code "65") (name "Net-(SQ_IN-P)") (class "Default")
      (node (ref "R41") (pin "1") (pinfunction "1_1") (pintype "passive"))
      (node (ref "SQ_IN") (pin "1") (pinfunction "P_1") (pintype "passive"))
    )
    (net (code "66") (name "Net-(SQ_MIX-P)") (class "Default")
      (node (ref "R41") (pin "2") (pinfunction "2_2") (pintype "passive"))
      (node (ref "R42") (pin "1") (pinfunction "1_1") (pintype "passive"))
      (node (ref "SQ_MIX") (pin "1") (pinfunction "P_1") (pintype "passive"))
    )
    (net (code "67") (name "Net-(TRIG_IN-P)") (class "Default")
      (node (ref "R23") (pin "1") (pinfunction "1_1") (pintype "passive"))
      (node (ref "TRIG_IN") (pin "1") (pinfunction "P_1") (pintype "passive"))
    )
    (net (code "68") (name "Net-(VCO_SAW_IN-P)") (class "Default")
      (node (ref "R11") (pin "1") (pinfunction "1_1") (pintype "passive"))
      (node (ref "VCO_SAW_IN") (pin "1") (pinfunction "P_1") (pintype "passive"))
    )
    (net (code "69") (name "Net-(VCO_SO_IN-P)") (class "Default")
      (node (ref "R9") (pin "1") (pinfunction "1_1") (pintype "passive"))
      (node (ref "VCO_SO_IN") (pin "1") (pinfunction "P_1") (pintype "passive"))
    )
  )
)
